# DC_Motor_Breakout.net
KiCad netlist of a schematic drawn in Altium Designer
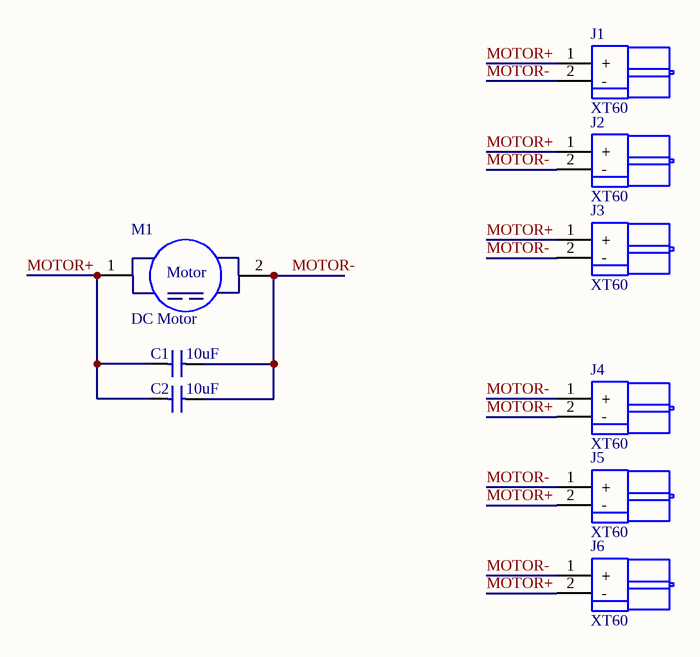
[diagram p0: DC_Motor_Breakout.SchDoc]

(export (version "E")
  (design (tool "Eeschema 10.0.6"))
  (components
    (comp (ref "C1")
      (value "10uF")
      (footprint "1210_Capacitor")
      (description "CAP CER 10UF 50V 10% X5R 1210")
      (fields
        (field (name "MANUFACTURER") "Taiyo Yuden")
        (field (name "Comment") "C_1210_10uF")
        (field (name "SVP CREATOR") "Matt Rogge")
      )
      (libsource (lib "capacitor") (part "C_1210_10uF"))
    )
    (comp (ref "C2")
      (value "10uF")
      (footprint "1210_Capacitor")
      (description "CAP CER 10UF 50V 10% X5R 1210")
      (fields
        (field (name "MANUFACTURER") "Taiyo Yuden")
        (field (name "Comment") "C_1210_10uF")
        (field (name "SVP CREATOR") "Matt Rogge")
      )
      (libsource (lib "capacitor") (part "C_1210_10uF"))
    )
    (comp (ref "J1")
      (value "XT60")
      (footprint "J_XT60_SMD_RA_Male")
      (description "60 Amp XT60 Connector")
      (libsource (lib "connector") (part "J_XT60"))
    )
    (comp (ref "J2")
      (value "XT60")
      (footprint "J_XT60_SMD_RA_Male")
      (description "60 Amp XT60 Connector")
      (libsource (lib "connector") (part "J_XT60"))
    )
    (comp (ref "J3")
      (value "XT60")
      (footprint "J_XT60_SMD_RA_Male")
      (description "60 Amp XT60 Connector")
      (libsource (lib "connector") (part "J_XT60"))
    )
    (comp (ref "J4")
      (value "XT60")
      (footprint "J_XT60_SMD_RA_Male")
      (description "60 Amp XT60 Connector")
      (libsource (lib "connector") (part "J_XT60"))
    )
    (comp (ref "J5")
      (value "XT60")
      (footprint "J_XT60_SMD_RA_Male")
      (description "60 Amp XT60 Connector")
      (libsource (lib "connector") (part "J_XT60"))
    )
    (comp (ref "J6")
      (value "XT60")
      (footprint "J_XT60_SMD_RA_Male")
      (description "60 Amp XT60 Connector")
      (libsource (lib "connector") (part "J_XT60"))
    )
    (comp (ref "M1")
      (value "DC Motor")
      (footprint "Motor_DC_36mm")
      (description "36mm DC Motor")
      (libsource (lib "misc") (part "M_DC_Motor"))
    )
  )
  (nets
    (net (code "1") (name "/MOTOR+") (class "Default")
      (node (ref "C1") (pin "2") (pinfunction "2_2") (pintype "passive"))
      (node (ref "C2") (pin "2") (pinfunction "2_2") (pintype "passive"))
      (node (ref "J1") (pin "1") (pinfunction "+_1") (pintype "passive"))
      (node (ref "J2") (pin "1") (pinfunction "+_1") (pintype "passive"))
      (node (ref "J3") (pin "1") (pinfunction "+_1") (pintype "passive"))
      (node (ref "J4") (pin "2") (pinfunction "-_2") (pintype "passive"))
      (node (ref "J5") (pin "2") (pinfunction "-_2") (pintype "passive"))
      (node (ref "J6") (pin "2") (pinfunction "-_2") (pintype "passive"))
      (node (ref "M1") (pin "1") (pinfunction "1_1") (pintype "passive"))
    )
    (net (code "2") (name "/MOTOR-") (class "Default")
      (node (ref "C1") (pin "1") (pinfunction "1_1") (pintype "passive"))
      (node (ref "C2") (pin "1") (pinfunction "1_1") (pintype "passive"))
      (node (ref "J1") (pin "2") (pinfunction "-_2") (pintype "passive"))
      (node (ref "J2") (pin "2") (pinfunction "-_2") (pintype "passive"))
      (node (ref "J3") (pin "2") (pinfunction "-_2") (pintype "passive"))
      (node (ref "J4") (pin "1") (pinfunction "+_1") (pintype "passive"))
      (node (ref "J5") (pin "1") (pinfunction "+_1") (pintype "passive"))
      (node (ref "J6") (pin "1") (pinfunction "+_1") (pintype "passive"))
      (node (ref "M1") (pin "2") (pinfunction "2_2") (pintype "passive"))
    )
  )
)
